# RECIEVER_CIRCUIT.net
KiCad netlist of a schematic drawn in EAGLE
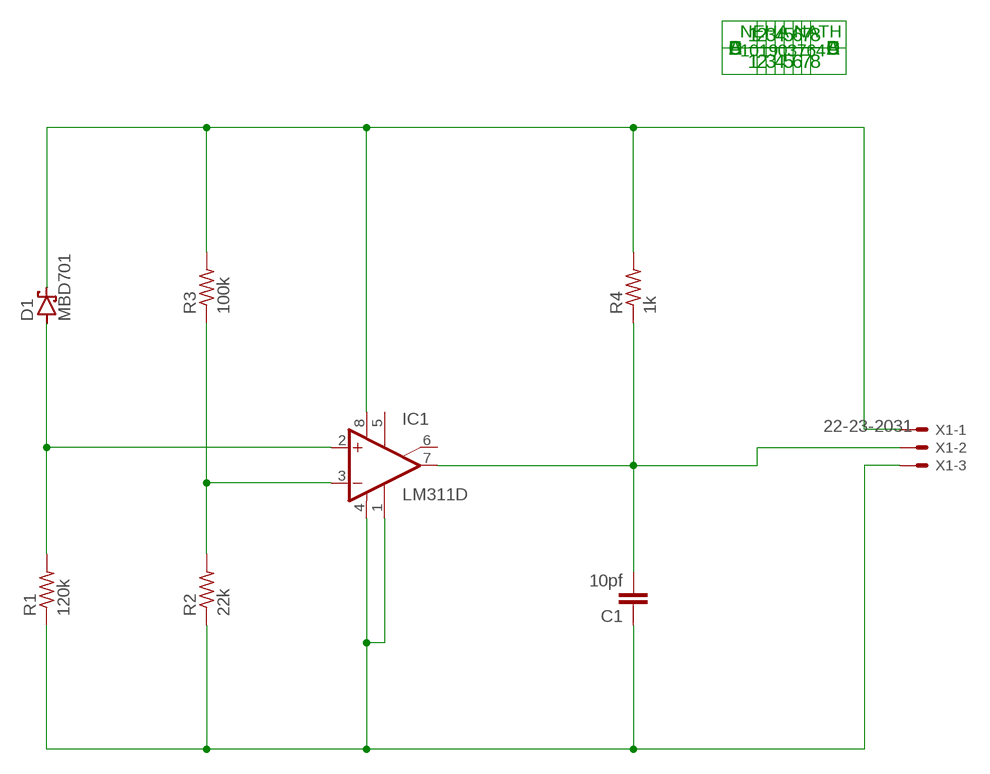
[diagram p0: schematic, sheet 1]

(export (version "E")
  (design (tool "Eeschema 10.0.6"))
  (components
    (comp (ref "C1")
      (value "10pf")
      (footprint "eagle-import:C2.5-4")
      (libsource (lib "eagle-import") (part "C2.5/4"))
    )
    (comp (ref "D1")
      (value "MBD701")
      (footprint "eagle-import:TO92H")
      (libsource (lib "eagle-import") (part "MBD701"))
    )
    (comp (ref "IC1")
      (value "LM311D")
      (footprint "eagle-import:SO08")
      (libsource (lib "eagle-import") (part "LM311D"))
    )
    (comp (ref "R1")
      (value "120k")
      (footprint "eagle-import:0207_15")
      (libsource (lib "eagle-import") (part "R-US_0207/15"))
    )
    (comp (ref "R2")
      (value "22k")
      (footprint "eagle-import:0207_15")
      (libsource (lib "eagle-import") (part "R-US_0207/15"))
    )
    (comp (ref "R3")
      (value "100k")
      (footprint "eagle-import:0207_15")
      (libsource (lib "eagle-import") (part "R-US_0207/15"))
    )
    (comp (ref "R4")
      (value "1k")
      (footprint "eagle-import:0207_15")
      (libsource (lib "eagle-import") (part "R-US_0207/15"))
    )
    (comp (ref "X1")
      (value "22-23-2031")
      (footprint "eagle-import:22-23-2031")
      (fields (field (name "MF") "MOLEX"))
      (libsource (lib "eagle-import") (part "22-23-2031"))
    )
  )
  (nets
    (net (code "1") (name "Net-(D1-A)") (class "Default")
      (node (ref "D1") (pin "1") (pinfunction "A_1") (pintype "passive"))
      (node (ref "IC1") (pin "2") (pinfunction "+IN_2") (pintype "input"))
      (node (ref "R1") (pin "2") (pinfunction "2_2") (pintype "passive"))
    )
    (net (code "2") (name "Net-(D1-C)") (class "Default")
      (node (ref "D1") (pin "2") (pinfunction "C_2") (pintype "passive"))
      (node (ref "IC1") (pin "8") (pinfunction "V+_8") (pintype "power_in"))
      (node (ref "R3") (pin "2") (pinfunction "2_2") (pintype "passive"))
      (node (ref "R4") (pin "2") (pinfunction "2_2") (pintype "passive"))
      (node (ref "X1") (pin "1") (pinfunction "S_1") (pintype "passive"))
    )
    (net (code "3") (name "Net-(IC1--IN)") (class "Default")
      (node (ref "IC1") (pin "3") (pinfunction "-IN_3") (pintype "input"))
      (node (ref "R2") (pin "2") (pinfunction "2_2") (pintype "passive"))
      (node (ref "R3") (pin "1") (pinfunction "1_1") (pintype "passive"))
    )
    (net (code "4") (name "Net-(IC1-GND)") (class "Default")
      (node (ref "C1") (pin "1") (pinfunction "1_1") (pintype "passive"))
      (node (ref "IC1") (pin "1") (pinfunction "GND_1") (pintype "passive"))
      (node (ref "IC1") (pin "4") (pinfunction "V-_4") (pintype "power_in"))
      (node (ref "R1") (pin "1") (pinfunction "1_1") (pintype "passive"))
      (node (ref "R2") (pin "1") (pinfunction "1_1") (pintype "passive"))
      (node (ref "X1") (pin "3") (pinfunction "S_3") (pintype "passive"))
    )
    (net (code "5") (name "Net-(IC1-OUT)") (class "Default")
      (node (ref "C1") (pin "2") (pinfunction "2_2") (pintype "passive"))
      (node (ref "IC1") (pin "7") (pinfunction "OUT_7") (pintype "output"))
      (node (ref "R4") (pin "1") (pinfunction "1_1") (pintype "passive"))
      (node (ref "X1") (pin "2") (pinfunction "S_2") (pintype "passive"))
    )
    (net (code "6") (name "unconnected-(IC1-ON-Pad5)") (class "Default")
      (node (ref "IC1") (pin "5") (pinfunction "ON_5") (pintype "passive"))
    )
    (net (code "7") (name "unconnected-(IC1-ON{slash}STR-Pad6)") (class "Default")
      (node (ref "IC1") (pin "6") (pinfunction "ON/STR_6") (pintype "passive"))
    )
  )
)
